# 15.net
KiCad netlist of a schematic drawn in Altium Designer
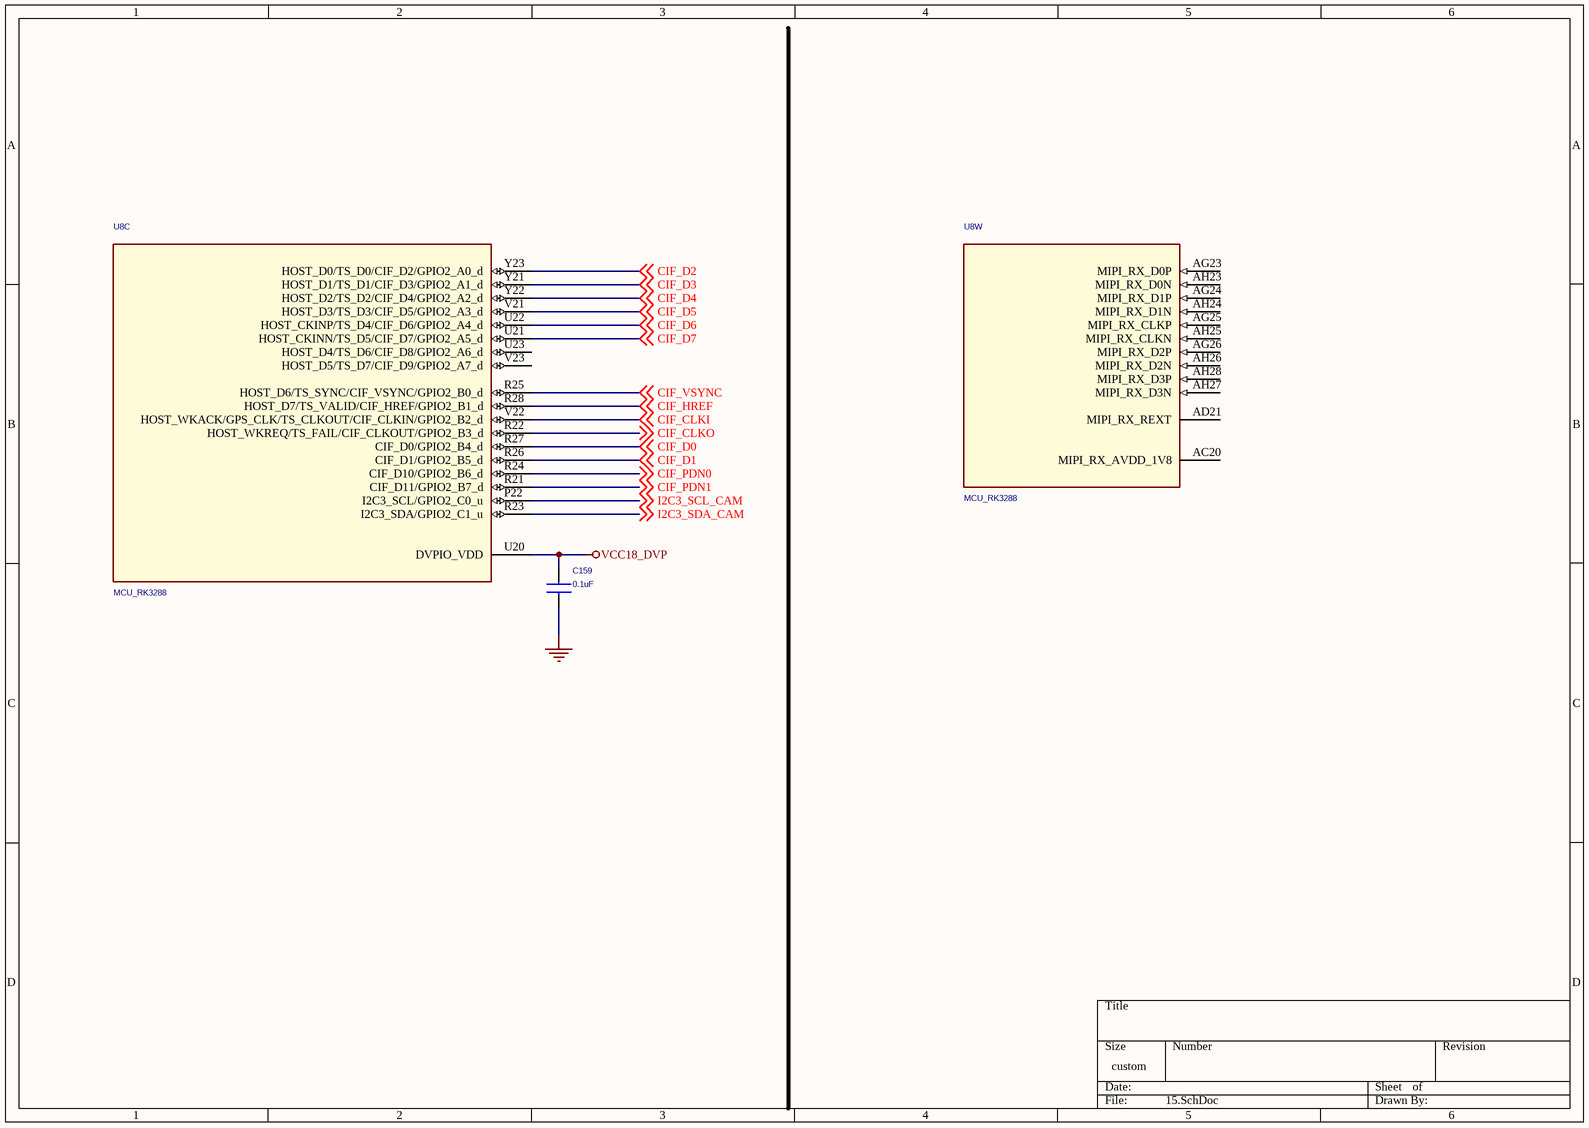
[diagram p0: 15.SchDoc]

(export (version "E")
  (design (tool "Eeschema 10.0.6"))
  (components
    (comp (ref "C159")
      (value "0.1uF")
      (footprint "C0603")
      (description "CAP,MLCC,1uF,+/-10%,X5R,6.3V,SMD0402")
      (libsource (lib "*") (part "CAP NP_Dup3"))
    )
    (comp (ref "U8")
      (value "MCU_RK3288")
      (footprint "BGA453-19X19")
      (libsource (lib "*") (part "MCU_RK3288_3"))
    )
  )
  (nets
    (net (code "1") (name "CIF_CLKI") (class "Default")
      (node (ref "U8") (pin "V22") (pinfunction "HOST_WKACK/GPS_CLK/TS_CLKOUT/CIF_CLKIN/GPIO2_B2_d_V22") (pintype "bidirectional"))
    )
    (net (code "2") (name "CIF_CLKO") (class "Default")
      (node (ref "U8") (pin "R22") (pinfunction "HOST_WKREQ/TS_FAIL/CIF_CLKOUT/GPIO2_B3_d_R22") (pintype "bidirectional"))
    )
    (net (code "3") (name "CIF_D0") (class "Default")
      (node (ref "U8") (pin "R27") (pinfunction "CIF_D0/GPIO2_B4_d_R27") (pintype "bidirectional"))
    )
    (net (code "4") (name "CIF_D1") (class "Default")
      (node (ref "U8") (pin "R26") (pinfunction "CIF_D1/GPIO2_B5_d_R26") (pintype "bidirectional"))
    )
    (net (code "5") (name "CIF_D2") (class "Default")
      (node (ref "U8") (pin "Y23") (pinfunction "HOST_D0/TS_D0/CIF_D2/GPIO2_A0_d_Y23") (pintype "bidirectional"))
    )
    (net (code "6") (name "CIF_D3") (class "Default")
      (node (ref "U8") (pin "Y21") (pinfunction "HOST_D1/TS_D1/CIF_D3/GPIO2_A1_d_Y21") (pintype "bidirectional"))
    )
    (net (code "7") (name "CIF_D4") (class "Default")
      (node (ref "U8") (pin "Y22") (pinfunction "HOST_D2/TS_D2/CIF_D4/GPIO2_A2_d_Y22") (pintype "bidirectional"))
    )
    (net (code "8") (name "CIF_D5") (class "Default")
      (node (ref "U8") (pin "V21") (pinfunction "HOST_D3/TS_D3/CIF_D5/GPIO2_A3_d_V21") (pintype "bidirectional"))
    )
    (net (code "9") (name "CIF_D6") (class "Default")
      (node (ref "U8") (pin "U22") (pinfunction "HOST_CKINP/TS_D4/CIF_D6/GPIO2_A4_d_U22") (pintype "bidirectional"))
    )
    (net (code "10") (name "CIF_D7") (class "Default")
      (node (ref "U8") (pin "U21") (pinfunction "HOST_CKINN/TS_D5/CIF_D7/GPIO2_A5_d_U21") (pintype "bidirectional"))
    )
    (net (code "11") (name "CIF_HREF") (class "Default")
      (node (ref "U8") (pin "R28") (pinfunction "HOST_D7/TS_VALID/CIF_HREF/GPIO2_B1_d_R28") (pintype "bidirectional"))
    )
    (net (code "12") (name "CIF_PDN0") (class "Default")
      (node (ref "U8") (pin "R24") (pinfunction "CIF_D10/GPIO2_B6_d_R24") (pintype "bidirectional"))
    )
    (net (code "13") (name "CIF_PDN1") (class "Default")
      (node (ref "U8") (pin "R21") (pinfunction "CIF_D11/GPIO2_B7_d_R21") (pintype "bidirectional"))
    )
    (net (code "14") (name "CIF_VSYNC") (class "Default")
      (node (ref "U8") (pin "R25") (pinfunction "HOST_D6/TS_SYNC/CIF_VSYNC/GPIO2_B0_d_R25") (pintype "bidirectional"))
    )
    (net (code "15") (name "GND") (class "Default")
      (node (ref "C159") (pin "2") (pinfunction "2_2") (pintype "passive"))
    )
    (net (code "16") (name "I2C3_SCL_CAM") (class "Default")
      (node (ref "U8") (pin "P22") (pinfunction "I2C3_SCL/GPIO2_C0_u_P22") (pintype "bidirectional"))
    )
    (net (code "17") (name "I2C3_SDA_CAM") (class "Default")
      (node (ref "U8") (pin "R23") (pinfunction "I2C3_SDA/GPIO2_C1_u_R23") (pintype "bidirectional"))
    )
    (net (code "18") (name "VCC18_DVP") (class "Default")
      (node (ref "C159") (pin "1") (pinfunction "1_1") (pintype "passive"))
      (node (ref "U8") (pin "U20") (pinfunction "DVPIO_VDD_U20") (pintype "power_in"))
    )
    (net (code "19") (name "unconnected-(U8C-HOST_D4{slash}TS_D6{slash}CIF_D8{slash}GPIO2_A6_d-PadU23)") (class "Default")
      (node (ref "U8") (pin "U23") (pinfunction "HOST_D4/TS_D6/CIF_D8/GPIO2_A6_d_U23") (pintype "bidirectional"))
    )
    (net (code "20") (name "unconnected-(U8C-HOST_D5{slash}TS_D7{slash}CIF_D9{slash}GPIO2_A7_d-PadV23)") (class "Default")
      (node (ref "U8") (pin "V23") (pinfunction "HOST_D5/TS_D7/CIF_D9/GPIO2_A7_d_V23") (pintype "bidirectional"))
    )
    (net (code "21") (name "unconnected-(U8W-MIPI_RX_AVDD_1V8-PadAC20)") (class "Default")
      (node (ref "U8") (pin "AC20") (pinfunction "MIPI_RX_AVDD_1V8_AC20") (pintype "passive"))
    )
    (net (code "22") (name "unconnected-(U8W-MIPI_RX_CLKN-PadAH25)") (class "Default")
      (node (ref "U8") (pin "AH25") (pinfunction "MIPI_RX_CLKN_AH25") (pintype "input"))
    )
    (net (code "23") (name "unconnected-(U8W-MIPI_RX_CLKP-PadAG25)") (class "Default")
      (node (ref "U8") (pin "AG25") (pinfunction "MIPI_RX_CLKP_AG25") (pintype "input"))
    )
    (net (code "24") (name "unconnected-(U8W-MIPI_RX_D0N-PadAH23)") (class "Default")
      (node (ref "U8") (pin "AH23") (pinfunction "MIPI_RX_D0N_AH23") (pintype "input"))
    )
    (net (code "25") (name "unconnected-(U8W-MIPI_RX_D0P-PadAG23)") (class "Default")
      (node (ref "U8") (pin "AG23") (pinfunction "MIPI_RX_D0P_AG23") (pintype "input"))
    )
    (net (code "26") (name "unconnected-(U8W-MIPI_RX_D1N-PadAH24)") (class "Default")
      (node (ref "U8") (pin "AH24") (pinfunction "MIPI_RX_D1N_AH24") (pintype "input"))
    )
    (net (code "27") (name "unconnected-(U8W-MIPI_RX_D1P-PadAG24)") (class "Default")
      (node (ref "U8") (pin "AG24") (pinfunction "MIPI_RX_D1P_AG24") (pintype "input"))
    )
    (net (code "28") (name "unconnected-(U8W-MIPI_RX_D2N-PadAH26)") (class "Default")
      (node (ref "U8") (pin "AH26") (pinfunction "MIPI_RX_D2N_AH26") (pintype "input"))
    )
    (net (code "29") (name "unconnected-(U8W-MIPI_RX_D2P-PadAG26)") (class "Default")
      (node (ref "U8") (pin "AG26") (pinfunction "MIPI_RX_D2P_AG26") (pintype "input"))
    )
    (net (code "30") (name "unconnected-(U8W-MIPI_RX_D3N-PadAH27)") (class "Default")
      (node (ref "U8") (pin "AH27") (pinfunction "MIPI_RX_D3N_AH27") (pintype "input"))
    )
    (net (code "31") (name "unconnected-(U8W-MIPI_RX_D3P-PadAH28)") (class "Default")
      (node (ref "U8") (pin "AH28") (pinfunction "MIPI_RX_D3P_AH28") (pintype "input"))
    )
    (net (code "32") (name "unconnected-(U8W-MIPI_RX_REXT-PadAD21)") (class "Default")
      (node (ref "U8") (pin "AD21") (pinfunction "MIPI_RX_REXT_AD21") (pintype "passive"))
    )
  )
)
